# Adafruit_Proximity_Trinkey.net
KiCad netlist of a schematic drawn in EAGLE
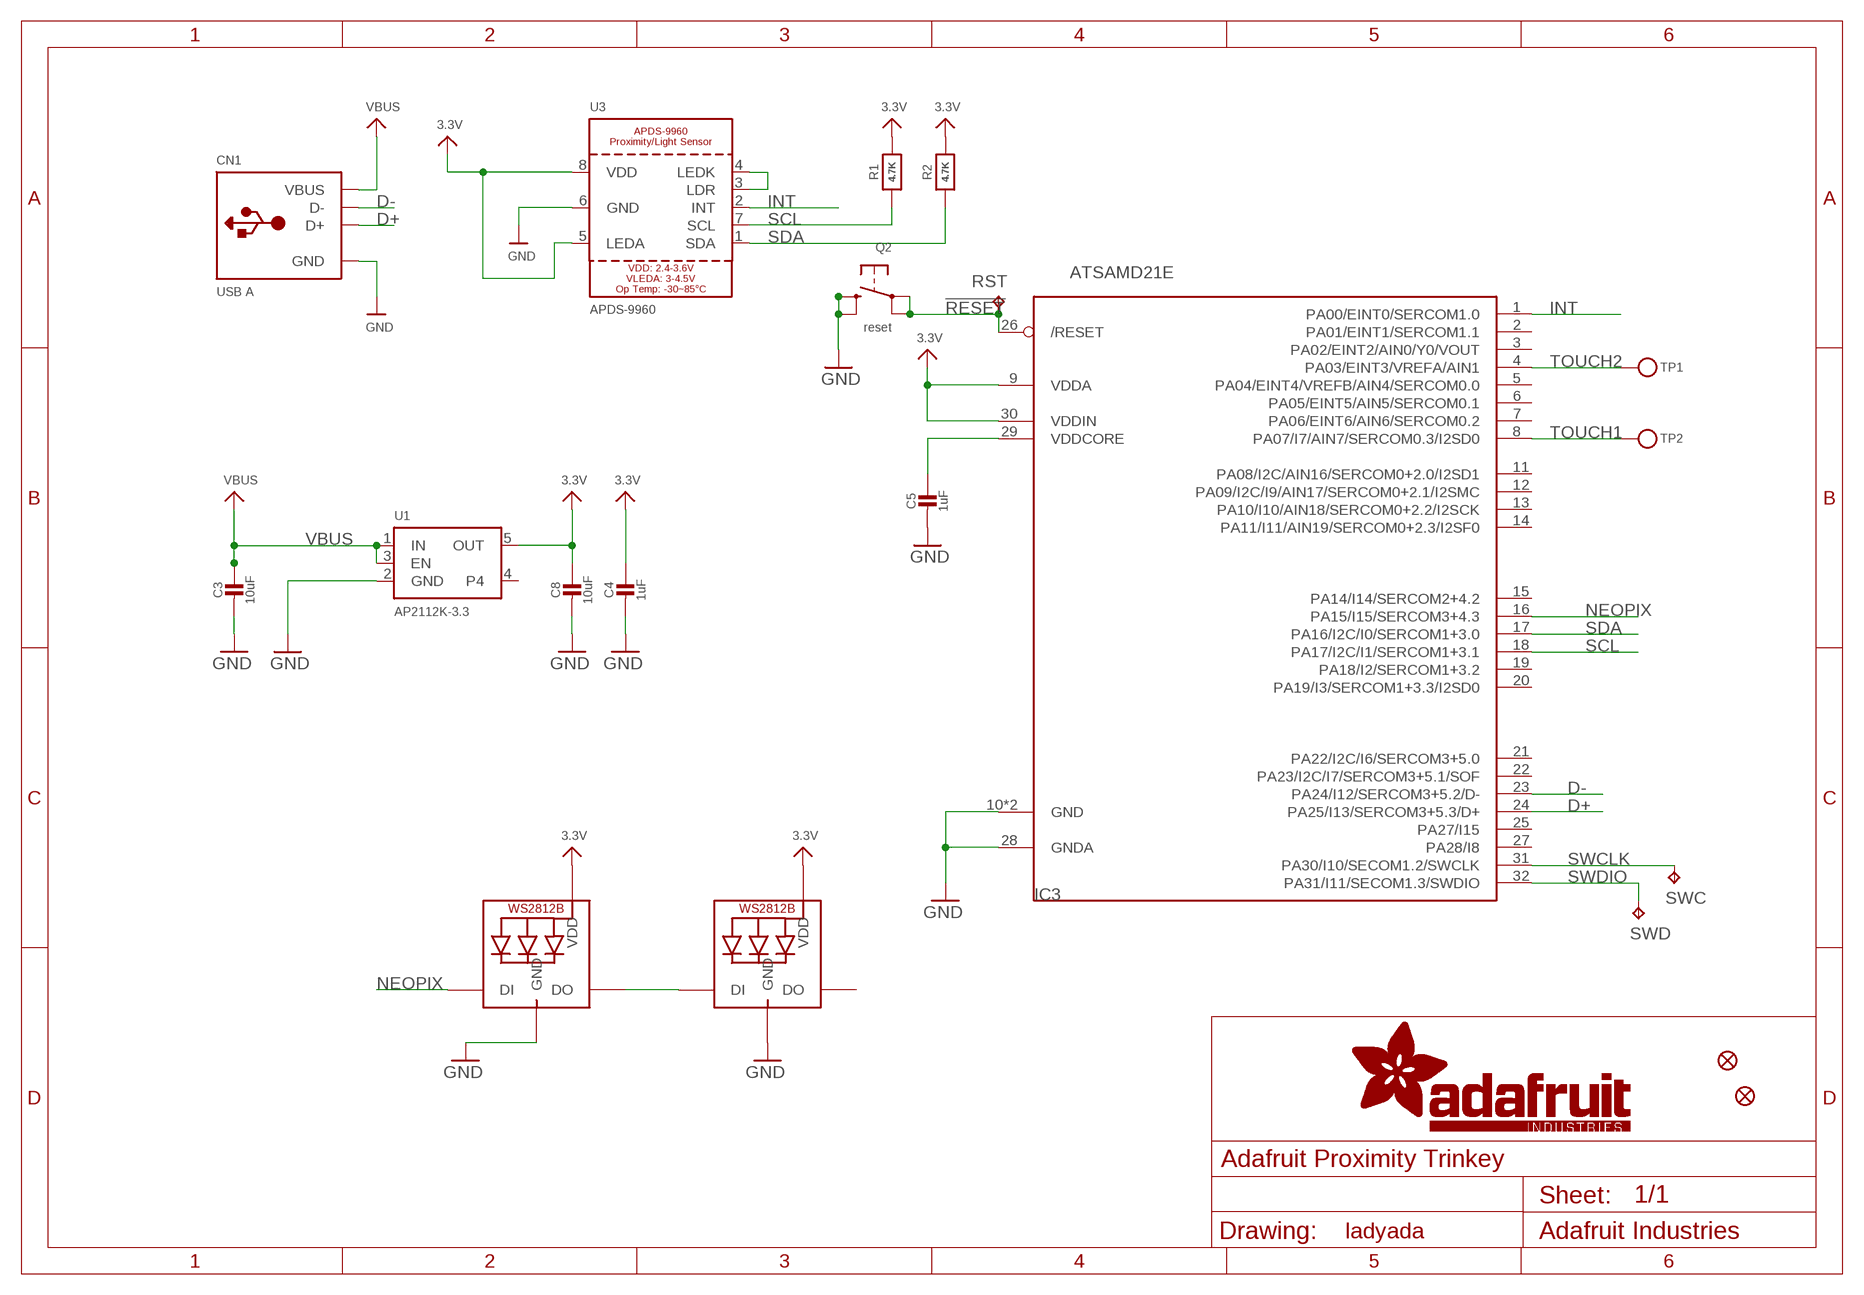
[diagram p0: schematic, sheet 1]

(export (version "E")
  (design (tool "Eeschema 10.0.6"))
  (components
    (comp (ref "C3")
      (value "10uF")
      (footprint "eagle-import:0805-NO")
      (libsource (lib "eagle-import") (part "CAP_CERAMIC0805-NOOUTLINE"))
    )
    (comp (ref "C4")
      (value "1uF")
      (footprint "eagle-import:0603-NO")
      (libsource (lib "eagle-import") (part "CAP_CERAMIC0603_NO"))
    )
    (comp (ref "C5")
      (value "1uF")
      (footprint "eagle-import:0603-NO")
      (libsource (lib "eagle-import") (part "CAP_CERAMIC0603_NO"))
    )
    (comp (ref "C8")
      (value "10uF")
      (footprint "eagle-import:0805-NO")
      (libsource (lib "eagle-import") (part "CAP_CERAMIC0805-NOOUTLINE"))
    )
    (comp (ref "CN1")
      (value "USB A")
      (footprint "eagle-import:USBA_PCB")
      (libsource (lib "eagle-import") (part "USB_TYPEAPCB"))
    )
    (comp (ref "FID1")
      (value "FIDUCIAL_1MM")
      (footprint "eagle-import:FIDUCIAL_1MM")
      (libsource (lib "eagle-import") (part "FIDUCIAL_1MM"))
    )
    (comp (ref "FID2")
      (value "FIDUCIAL_1MM")
      (footprint "eagle-import:FIDUCIAL_1MM")
      (libsource (lib "eagle-import") (part "FIDUCIAL_1MM"))
    )
    (comp (ref "IC3")
      (value "ATSAMD21E")
      (footprint "eagle-import:QFN32_5MM")
      (libsource (lib "eagle-import") (part "ATSAMD21E"))
    )
    (comp (ref "LED1")
      (value "WS2812B3535")
      (footprint "eagle-import:LED3535")
      (libsource (lib "eagle-import") (part "WS2812B3535"))
    )
    (comp (ref "LED2")
      (value "WS2812B3535")
      (footprint "eagle-import:LED3535")
      (libsource (lib "eagle-import") (part "WS2812B3535"))
    )
    (comp (ref "Q2")
      (value "reset")
      (footprint "eagle-import:BTN_KMR2_4.6X2.8")
      (libsource (lib "eagle-import") (part "SWITCH_TACT_SMT4.6X2.8"))
    )
    (comp (ref "R1")
      (value "4.7K")
      (footprint "eagle-import:0603-NO")
      (libsource (lib "eagle-import") (part "RESISTOR_0603_NOOUT"))
    )
    (comp (ref "R2")
      (value "4.7K")
      (footprint "eagle-import:0603-NO")
      (libsource (lib "eagle-import") (part "RESISTOR_0603_NOOUT"))
    )
    (comp (ref "RST")
      (value "TPTP16R")
      (footprint "eagle-import:TP16R")
      (libsource (lib "eagle-import") (part "TPTP16R"))
    )
    (comp (ref "SWC")
      (value "TPTP15R")
      (footprint "eagle-import:TP15R")
      (libsource (lib "eagle-import") (part "TPTP15R"))
    )
    (comp (ref "SWD")
      (value "TPTP16R")
      (footprint "eagle-import:TP16R")
      (libsource (lib "eagle-import") (part "TPTP16R"))
    )
    (comp (ref "TP1")
      (value "TESTPOINTROUND1.5MMNO")
      (footprint "eagle-import:TESTPOINT_ROUND_1.5MM_NO")
      (libsource (lib "eagle-import") (part "TESTPOINTROUND1.5MMNO"))
    )
    (comp (ref "TP2")
      (value "TESTPOINTROUND1.5MMNO")
      (footprint "eagle-import:TESTPOINT_ROUND_1.5MM_NO")
      (libsource (lib "eagle-import") (part "TESTPOINTROUND1.5MMNO"))
    )
    (comp (ref "U1")
      (value "AP2112K-3.3")
      (footprint "eagle-import:SOT23-5")
      (libsource (lib "eagle-import") (part "VREG_SOT23-5"))
    )
    (comp (ref "U3")
      (value "APDS-9960")
      (footprint "eagle-import:APDS-9960")
      (libsource (lib "eagle-import") (part "APDS-9960"))
    )
  )
  (nets
    (net (code "1") (name "/D+") (class "Default")
      (node (ref "CN1") (pin "USB_PLUS") (pinfunction "D+_USB_PLUS") (pintype "bidirectional"))
      (node (ref "IC3") (pin "24") (pinfunction "PA25/I13/SERCOM3+5.3/D+_24") (pintype "bidirectional"))
    )
    (net (code "2") (name "/D-") (class "Default")
      (node (ref "CN1") (pin "USB_NEG") (pinfunction "D-_USB_NEG") (pintype "bidirectional"))
      (node (ref "IC3") (pin "23") (pinfunction "PA24/I12/SERCOM3+5.2/D-_23") (pintype "bidirectional"))
    )
    (net (code "3") (name "/INT") (class "Default")
      (node (ref "IC3") (pin "1") (pinfunction "PA00/EINT0/SERCOM1.0_1") (pintype "bidirectional"))
      (node (ref "U3") (pin "2") (pinfunction "INT_2") (pintype "output"))
    )
    (net (code "4") (name "/NEOPIX") (class "Default")
      (node (ref "IC3") (pin "16") (pinfunction "PA15/I15/SERCOM3+4.3_16") (pintype "bidirectional"))
      (node (ref "LED2") (pin "1") (pinfunction "DI_1") (pintype "input"))
    )
    (net (code "5") (name "/SCL") (class "Default")
      (node (ref "IC3") (pin "18") (pinfunction "PA17/I2C/I1/SERCOM1+3.1_18") (pintype "bidirectional"))
      (node (ref "R1") (pin "1") (pinfunction "1_1") (pintype "passive"))
      (node (ref "U3") (pin "7") (pinfunction "SCL_7") (pintype "input"))
    )
    (net (code "6") (name "/SDA") (class "Default")
      (node (ref "IC3") (pin "17") (pinfunction "PA16/I2C/I0/SERCOM1+3.0_17") (pintype "bidirectional"))
      (node (ref "R2") (pin "1") (pinfunction "1_1") (pintype "passive"))
      (node (ref "U3") (pin "1") (pinfunction "SDA_1") (pintype "bidirectional"))
    )
    (net (code "7") (name "/SWCLK") (class "Default")
      (node (ref "IC3") (pin "31") (pinfunction "PA30/I10/SECOM1.2/SWCLK_31") (pintype "bidirectional"))
      (node (ref "SWC") (pin "TP") (pinfunction "TP_TP") (pintype "input"))
    )
    (net (code "8") (name "/SWDIO") (class "Default")
      (node (ref "IC3") (pin "32") (pinfunction "PA31/I11/SECOM1.3/SWDIO_32") (pintype "bidirectional"))
      (node (ref "SWD") (pin "TP") (pinfunction "TP_TP") (pintype "input"))
    )
    (net (code "9") (name "/TOUCH1") (class "Default")
      (node (ref "IC3") (pin "8") (pinfunction "PA07/I7/AIN7/SERCOM0.3/I2SD0_8") (pintype "bidirectional"))
      (node (ref "TP2") (pin "P$1") (pinfunction "P$1_P$1") (pintype "bidirectional"))
    )
    (net (code "10") (name "/TOUCH2") (class "Default")
      (node (ref "IC3") (pin "4") (pinfunction "PA03/EINT3/VREFA/AIN1_4") (pintype "bidirectional"))
      (node (ref "TP1") (pin "P$1") (pinfunction "P$1_P$1") (pintype "bidirectional"))
    )
    (net (code "11") (name "/~{RESET}") (class "Default")
      (node (ref "IC3") (pin "26") (pinfunction "/RESET_26") (pintype "bidirectional"))
      (node (ref "Q2") (pin "A") (pinfunction "P_A") (pintype "passive"))
      (node (ref "Q2") (pin "A'") (pinfunction "P1_A'") (pintype "passive"))
      (node (ref "RST") (pin "TP") (pinfunction "TP_TP") (pintype "input"))
    )
    (net (code "12") (name "3.3V") (class "Default")
      (node (ref "C4") (pin "1") (pinfunction "1_1") (pintype "passive"))
      (node (ref "C8") (pin "1") (pinfunction "1_1") (pintype "passive"))
      (node (ref "IC3") (pin "30") (pinfunction "VDDIN_30") (pintype "power_in"))
      (node (ref "IC3") (pin "9") (pinfunction "VDDA_9") (pintype "power_in"))
      (node (ref "LED1") (pin "2") (pinfunction "VDD_2") (pintype "power_in"))
      (node (ref "LED2") (pin "2") (pinfunction "VDD_2") (pintype "power_in"))
      (node (ref "R1") (pin "2") (pinfunction "2_2") (pintype "passive"))
      (node (ref "R2") (pin "2") (pinfunction "2_2") (pintype "passive"))
      (node (ref "U1") (pin "5") (pinfunction "OUT_5") (pintype "power_in"))
      (node (ref "U3") (pin "5") (pinfunction "LEDA_5") (pintype "power_in"))
      (node (ref "U3") (pin "8") (pinfunction "VDD_8") (pintype "power_in"))
    )
    (net (code "13") (name "GND") (class "Default")
      (node (ref "C3") (pin "2") (pinfunction "2_2") (pintype "passive"))
      (node (ref "C4") (pin "2") (pinfunction "2_2") (pintype "passive"))
      (node (ref "C5") (pin "2") (pinfunction "2_2") (pintype "passive"))
      (node (ref "C8") (pin "2") (pinfunction "2_2") (pintype "passive"))
      (node (ref "CN1") (pin "GND") (pinfunction "GND_GND") (pintype "power_in"))
      (node (ref "IC3") (pin "10") (pinfunction "GND_10") (pintype "power_in"))
      (node (ref "IC3") (pin "28") (pinfunction "GNDA_28") (pintype "power_in"))
      (node (ref "IC3") (pin "33") (pinfunction "GND_33") (pintype "power_in"))
      (node (ref "LED1") (pin "4") (pinfunction "GND_4") (pintype "power_in"))
      (node (ref "LED2") (pin "4") (pinfunction "GND_4") (pintype "power_in"))
      (node (ref "Q2") (pin "B") (pinfunction "S_B") (pintype "passive"))
      (node (ref "Q2") (pin "B'") (pinfunction "S1_B'") (pintype "passive"))
      (node (ref "U1") (pin "2") (pinfunction "GND_2") (pintype "power_in"))
      (node (ref "U3") (pin "6") (pinfunction "GND_6") (pintype "power_in"))
    )
    (net (code "14") (name "Net-(IC3-VDDCORE)") (class "Default")
      (node (ref "C5") (pin "1") (pinfunction "1_1") (pintype "passive"))
      (node (ref "IC3") (pin "29") (pinfunction "VDDCORE_29") (pintype "power_in"))
    )
    (net (code "15") (name "Net-(LED1-DI)") (class "Default")
      (node (ref "LED1") (pin "1") (pinfunction "DI_1") (pintype "input"))
      (node (ref "LED2") (pin "3") (pinfunction "DO_3") (pintype "output"))
    )
    (net (code "16") (name "Net-(U3-LDR)") (class "Default")
      (node (ref "U3") (pin "3") (pinfunction "LDR_3") (pintype "bidirectional"))
      (node (ref "U3") (pin "4") (pinfunction "LEDK_4") (pintype "bidirectional"))
    )
    (net (code "17") (name "VBUS") (class "Default")
      (node (ref "C3") (pin "1") (pinfunction "1_1") (pintype "passive"))
      (node (ref "CN1") (pin "VCC") (pinfunction "VBUS_VCC") (pintype "power_in"))
      (node (ref "U1") (pin "1") (pinfunction "IN_1") (pintype "power_in"))
      (node (ref "U1") (pin "3") (pinfunction "EN_3") (pintype "input"))
    )
    (net (code "18") (name "unconnected-(IC3-PA01{slash}EINT1{slash}SERCOM1.1-Pad2)") (class "Default")
      (node (ref "IC3") (pin "2") (pinfunction "PA01/EINT1/SERCOM1.1_2") (pintype "bidirectional"))
    )
    (net (code "19") (name "unconnected-(IC3-PA02{slash}EINT2{slash}AIN0{slash}Y0{slash}VOUT-Pad3)") (class "Default")
      (node (ref "IC3") (pin "3") (pinfunction "PA02/EINT2/AIN0/Y0/VOUT_3") (pintype "bidirectional"))
    )
    (net (code "20") (name "unconnected-(IC3-PA04{slash}EINT4{slash}VREFB{slash}AIN4{slash}SERCOM0.0-Pad5)") (class "Default")
      (node (ref "IC3") (pin "5") (pinfunction "PA04/EINT4/VREFB/AIN4/SERCOM0.0_5") (pintype "bidirectional"))
    )
    (net (code "21") (name "unconnected-(IC3-PA05{slash}EINT5{slash}AIN5{slash}SERCOM0.1-Pad6)") (class "Default")
      (node (ref "IC3") (pin "6") (pinfunction "PA05/EINT5/AIN5/SERCOM0.1_6") (pintype "bidirectional"))
    )
    (net (code "22") (name "unconnected-(IC3-PA06{slash}EINT6{slash}AIN6{slash}SERCOM0.2-Pad7)") (class "Default")
      (node (ref "IC3") (pin "7") (pinfunction "PA06/EINT6/AIN6/SERCOM0.2_7") (pintype "bidirectional"))
    )
    (net (code "23") (name "unconnected-(IC3-PA08{slash}I2C{slash}AIN16{slash}SERCOM0+2.0{slash}I2SD1-Pad11)") (class "Default")
      (node (ref "IC3") (pin "11") (pinfunction "PA08/I2C/AIN16/SERCOM0+2.0/I2SD1_11") (pintype "bidirectional"))
    )
    (net (code "24") (name "unconnected-(IC3-PA09{slash}I2C{slash}I9{slash}AIN17{slash}SERCOM0+2.1{slash}I2SMC-Pad12)") (class "Default")
      (node (ref "IC3") (pin "12") (pinfunction "PA09/I2C/I9/AIN17/SERCOM0+2.1/I2SMC_12") (pintype "bidirectional"))
    )
    (net (code "25") (name "unconnected-(IC3-PA10{slash}I10{slash}AIN18{slash}SERCOM0+2.2{slash}I2SCK-Pad13)") (class "Default")
      (node (ref "IC3") (pin "13") (pinfunction "PA10/I10/AIN18/SERCOM0+2.2/I2SCK_13") (pintype "bidirectional"))
    )
    (net (code "26") (name "unconnected-(IC3-PA11{slash}I11{slash}AIN19{slash}SERCOM0+2.3{slash}I2SF0-Pad14)") (class "Default")
      (node (ref "IC3") (pin "14") (pinfunction "PA11/I11/AIN19/SERCOM0+2.3/I2SF0_14") (pintype "bidirectional"))
    )
    (net (code "27") (name "unconnected-(IC3-PA14{slash}I14{slash}SERCOM2+4.2-Pad15)") (class "Default")
      (node (ref "IC3") (pin "15") (pinfunction "PA14/I14/SERCOM2+4.2_15") (pintype "bidirectional"))
    )
    (net (code "28") (name "unconnected-(IC3-PA18{slash}I2{slash}SERCOM1+3.2-Pad19)") (class "Default")
      (node (ref "IC3") (pin "19") (pinfunction "PA18/I2/SERCOM1+3.2_19") (pintype "bidirectional"))
    )
    (net (code "29") (name "unconnected-(IC3-PA19{slash}I3{slash}SERCOM1+3.3{slash}I2SD0-Pad20)") (class "Default")
      (node (ref "IC3") (pin "20") (pinfunction "PA19/I3/SERCOM1+3.3/I2SD0_20") (pintype "bidirectional"))
    )
    (net (code "30") (name "unconnected-(IC3-PA22{slash}I2C{slash}I6{slash}SERCOM3+5.0-Pad21)") (class "Default")
      (node (ref "IC3") (pin "21") (pinfunction "PA22/I2C/I6/SERCOM3+5.0_21") (pintype "bidirectional"))
    )
    (net (code "31") (name "unconnected-(IC3-PA23{slash}I2C{slash}I7{slash}SERCOM3+5.1{slash}SOF-Pad22)") (class "Default")
      (node (ref "IC3") (pin "22") (pinfunction "PA23/I2C/I7/SERCOM3+5.1/SOF_22") (pintype "bidirectional"))
    )
    (net (code "32") (name "unconnected-(IC3-PA27{slash}I15-Pad25)") (class "Default")
      (node (ref "IC3") (pin "25") (pinfunction "PA27/I15_25") (pintype "bidirectional"))
    )
    (net (code "33") (name "unconnected-(IC3-PA28{slash}I8-Pad27)") (class "Default")
      (node (ref "IC3") (pin "27") (pinfunction "PA28/I8_27") (pintype "bidirectional"))
    )
    (net (code "34") (name "unconnected-(LED1-DO-Pad3)") (class "Default")
      (node (ref "LED1") (pin "3") (pinfunction "DO_3") (pintype "output"))
    )
    (net (code "35") (name "unconnected-(U1-P4-Pad4)") (class "Default")
      (node (ref "U1") (pin "4") (pinfunction "P4_4") (pintype "bidirectional"))
    )
  )
)
